# schematic.net
KiCad netlist of a schematic drawn in EasyEDA
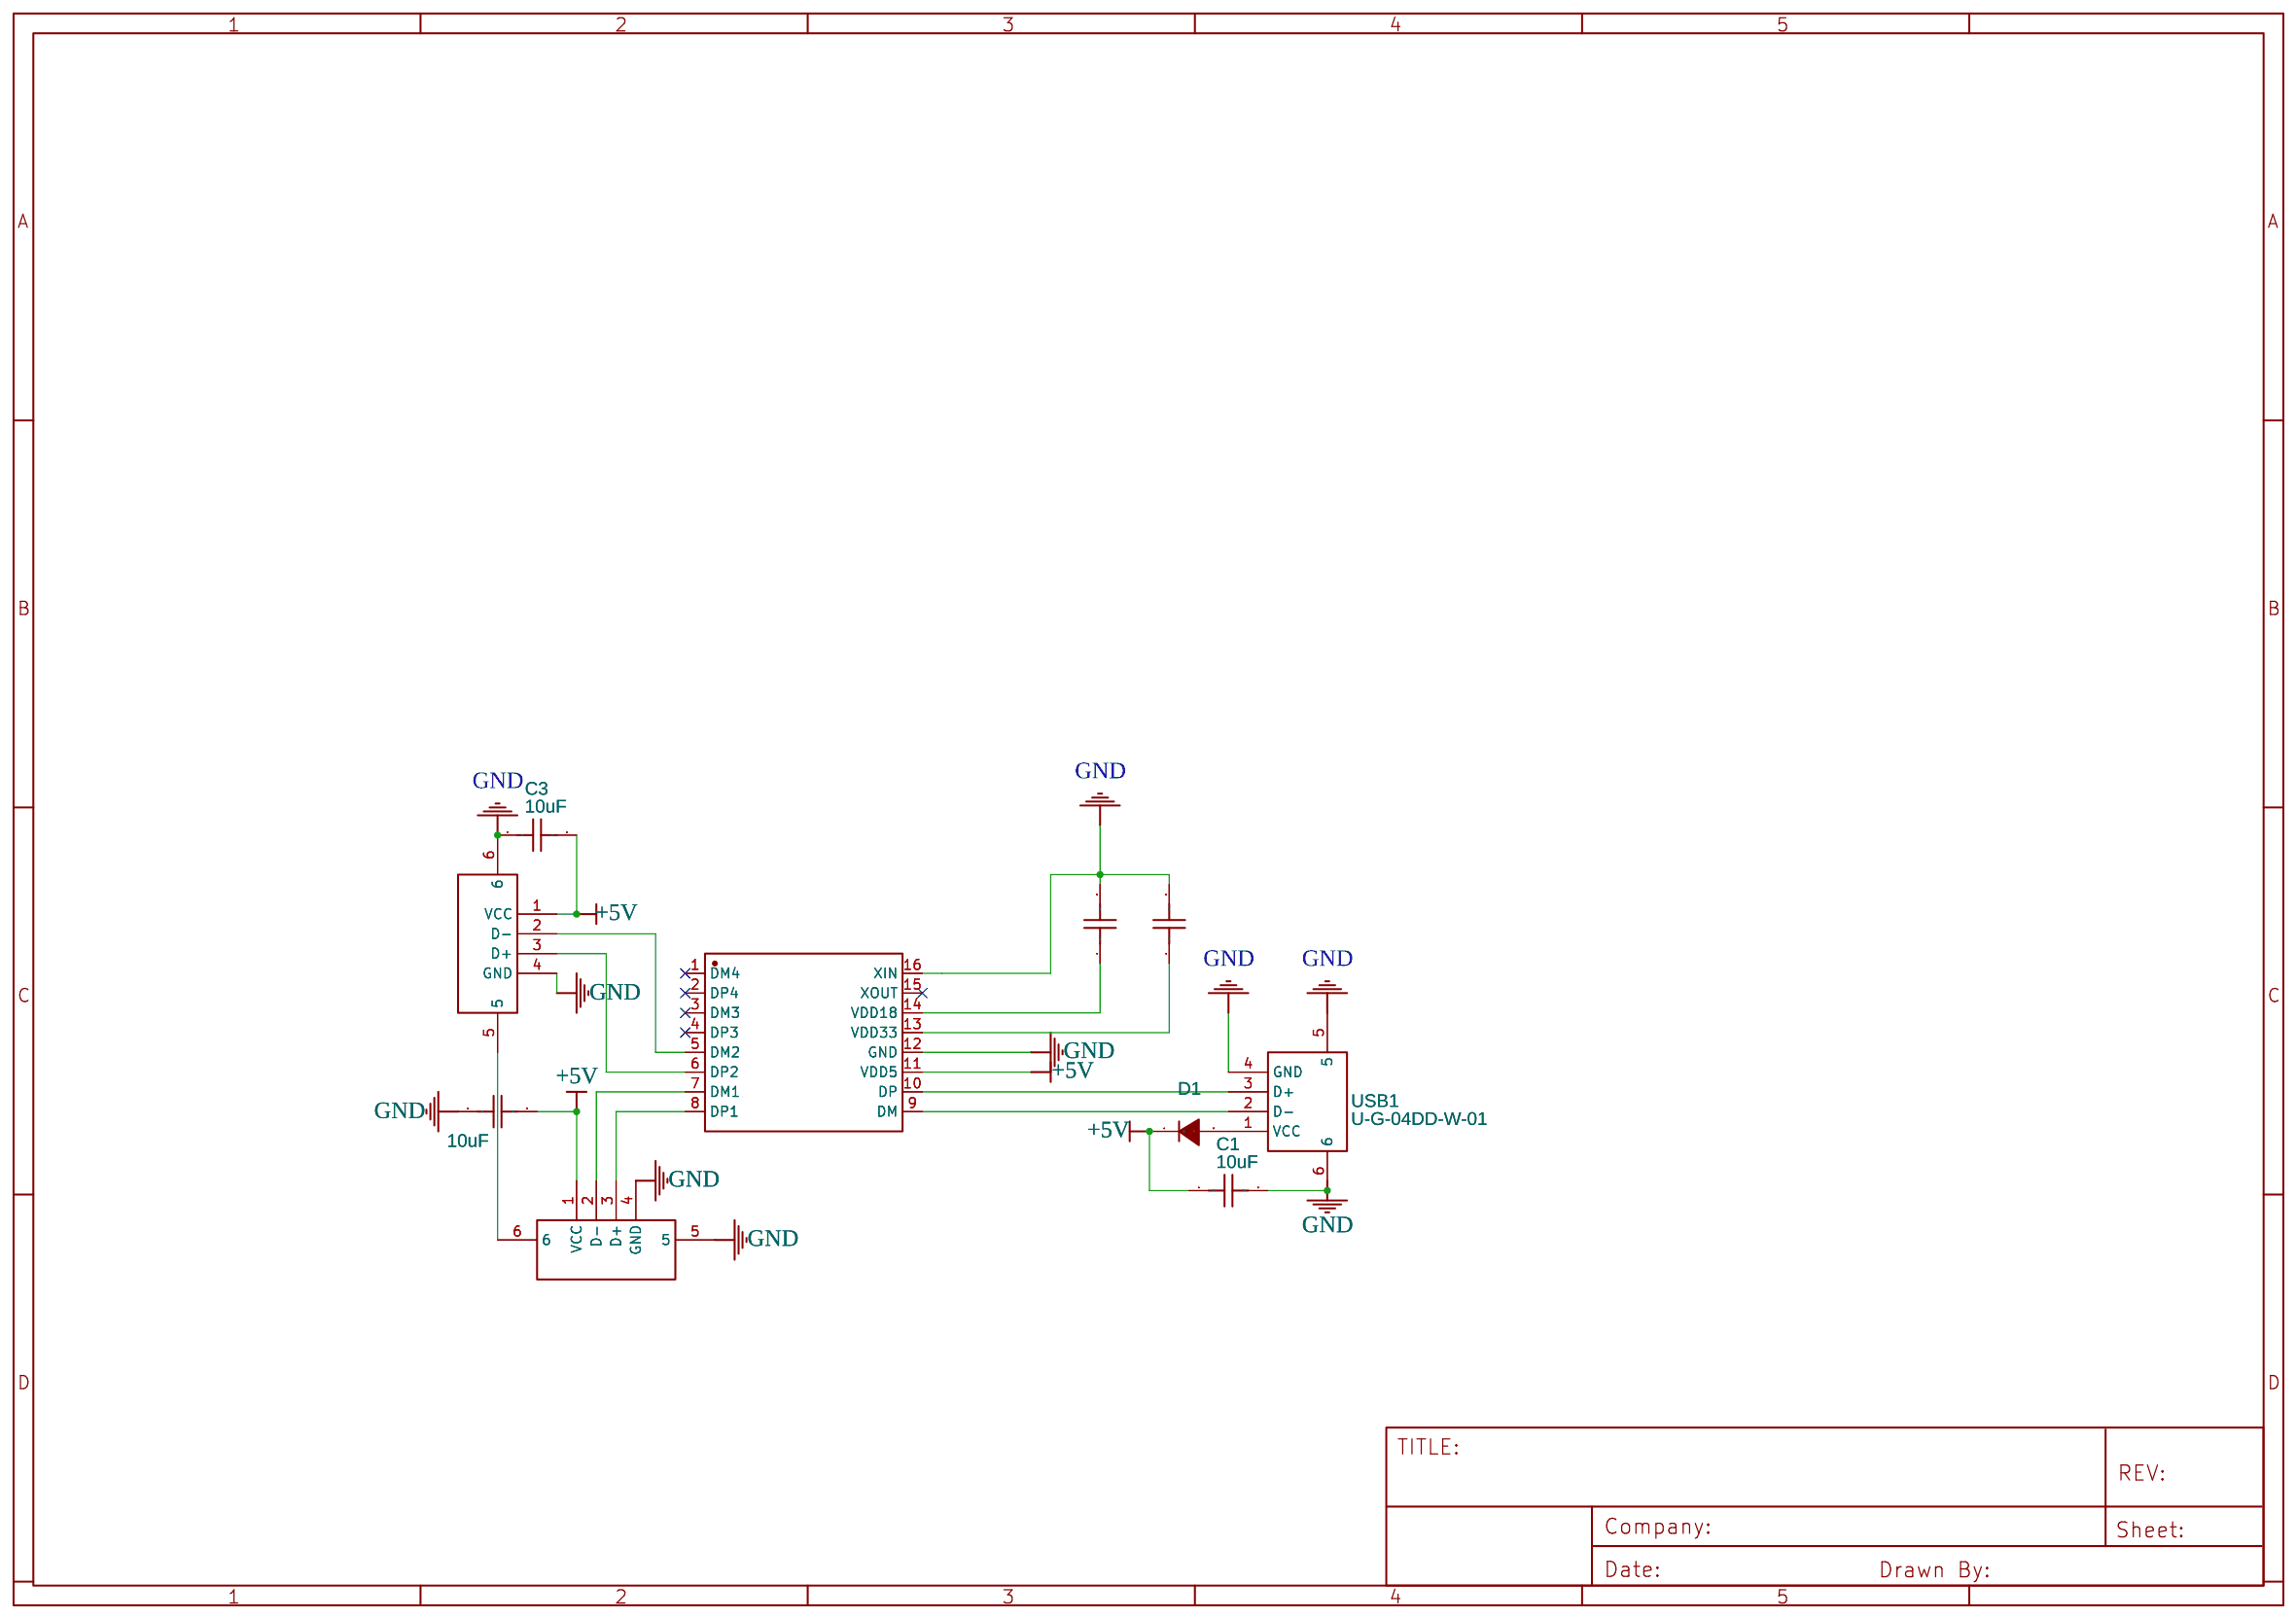
[diagram p0: schematic sheet]

(export (version "E")
  (design (tool "Eeschema 10.0.6"))
  (components
    (comp (ref "C1")
      (value "10uF")
      (fields
        (field (name "Manufacturer Part") "CL10A106KP8NNNC")
        (field (name "Manufacturer") "SAMSUNG(三星)")
      )
      (libsource (lib "") (part "CL10A106KP8NNNC"))
    )
    (comp (ref "C2")
      (value "10uF")
      (fields
        (field (name "Manufacturer Part") "CL10A106KP8NNNC")
        (field (name "Manufacturer") "SAMSUNG(三星)")
      )
      (libsource (lib "") (part "CL10A106KP8NNNC"))
    )
    (comp (ref "C3")
      (value "10uF")
      (fields
        (field (name "Manufacturer Part") "CL10A106KP8NNNC")
        (field (name "Manufacturer") "SAMSUNG(三星)")
      )
      (libsource (lib "") (part "CL10A106KP8NNNC"))
    )
    (comp (ref "C5")
      (value "10uF")
      (fields
        (field (name "Manufacturer Part") "CL10A106KP8NNNC")
        (field (name "Manufacturer") "SAMSUNG(三星)")
      )
      (libsource (lib "") (part "CL10A106KP8NNNC_1"))
    )
    (comp (ref "C6")
      (value "10uF")
      (fields
        (field (name "Manufacturer Part") "CL10A106KP8NNNC")
        (field (name "Manufacturer") "SAMSUNG(三星)")
      )
      (libsource (lib "") (part "CL10A106KP8NNNC_1"))
    )
    (comp (ref "D1")
      (value "NSR0320MW2T1G")
      (fields (field (name "Manufacturer") "onsemi(安森美)"))
      (libsource (lib "") (part "NSR0320MW2T1G"))
    )
    (comp (ref "U1")
      (value "SL2.1A")
      (fields (field (name "Manufacturer") "CoreChips(和芯润德)"))
      (libsource (lib "") (part "SL2.1A"))
    )
    (comp (ref "USB1")
      (value "U-G-04DD-W-01")
      (fields (field (name "Manufacturer Part") "U-G-O4DD-W-1") (field (name "Manufacturer") "韩国韩荣"))
      (libsource (lib "") (part "U-G-04DD-W-01"))
    )
    (comp (ref "USB3")
      (value "USB-AF-90-14.4X13.6-H7.0-DIP")
      (fields (field (name "Manufacturer Part") "903-131A1011D10100") (field (name "Manufacturer") "精拓金"))
      (libsource (lib "") (part "USB-AF-90-14.4X13.6-H7.0-DIP_1"))
    )
    (comp (ref "USB4")
      (value "USB-AF-90-14.4X13.6-H7.0-DIP")
      (fields (field (name "Manufacturer Part") "903-131A1011D10100") (field (name "Manufacturer") "精拓金"))
      (libsource (lib "") (part "USB-AF-90-14.4X13.6-H7.0-DIP"))
    )
  )
  (nets
    (net (code "1") (name "+5V") (class "Default")
      (node (ref "C1") (pin "1") (pinfunction "1_1") (pintype "unspecified"))
      (node (ref "C2") (pin "2") (pinfunction "2_2") (pintype "unspecified"))
      (node (ref "C3") (pin "2") (pinfunction "2_2") (pintype "unspecified"))
      (node (ref "D1") (pin "1") (pinfunction "C_1") (pintype "unspecified"))
      (node (ref "U1") (pin "11") (pinfunction "VDD5_11") (pintype "unspecified"))
      (node (ref "USB3") (pin "1") (pinfunction "VCC_1") (pintype "unspecified"))
      (node (ref "USB4") (pin "1") (pinfunction "VCC_1") (pintype "unspecified"))
    )
    (net (code "2") (name "GND") (class "Default")
      (node (ref "C1") (pin "2") (pinfunction "2_2") (pintype "unspecified"))
      (node (ref "C2") (pin "1") (pinfunction "1_1") (pintype "unspecified"))
      (node (ref "C3") (pin "1") (pinfunction "1_1") (pintype "unspecified"))
      (node (ref "C5") (pin "2") (pinfunction "2_2") (pintype "unspecified"))
      (node (ref "C6") (pin "2") (pinfunction "2_2") (pintype "unspecified"))
      (node (ref "U1") (pin "12") (pinfunction "GND_12") (pintype "unspecified"))
      (node (ref "U1") (pin "16") (pinfunction "XIN_16") (pintype "unspecified"))
      (node (ref "USB1") (pin "4") (pinfunction "GND_4") (pintype "unspecified"))
      (node (ref "USB1") (pin "5") (pinfunction "5_5") (pintype "unspecified"))
      (node (ref "USB1") (pin "6") (pinfunction "6_6") (pintype "unspecified"))
      (node (ref "USB3") (pin "4") (pinfunction "GND_4") (pintype "unspecified"))
      (node (ref "USB3") (pin "5") (pinfunction "5_5") (pintype "unspecified"))
      (node (ref "USB4") (pin "4") (pinfunction "GND_4") (pintype "unspecified"))
      (node (ref "USB4") (pin "6") (pinfunction "6_6") (pintype "unspecified"))
    )
    (net (code "3") (name "Net-(D1-A)") (class "Default")
      (node (ref "D1") (pin "2") (pinfunction "A_2") (pintype "unspecified"))
      (node (ref "USB1") (pin "1") (pinfunction "VCC_1") (pintype "unspecified"))
    )
    (net (code "4") (name "Net-(U1-DM)") (class "Default")
      (node (ref "U1") (pin "9") (pinfunction "DM_9") (pintype "unspecified"))
      (node (ref "USB1") (pin "2") (pinfunction "D-_2") (pintype "unspecified"))
    )
    (net (code "5") (name "Net-(U1-DM1)") (class "Default")
      (node (ref "U1") (pin "7") (pinfunction "DM1_7") (pintype "unspecified"))
      (node (ref "USB3") (pin "2") (pinfunction "D-_2") (pintype "unspecified"))
    )
    (net (code "6") (name "Net-(U1-DM2)") (class "Default")
      (node (ref "U1") (pin "5") (pinfunction "DM2_5") (pintype "unspecified"))
      (node (ref "USB4") (pin "2") (pinfunction "D-_2") (pintype "unspecified"))
    )
    (net (code "7") (name "Net-(U1-DP)") (class "Default")
      (node (ref "U1") (pin "10") (pinfunction "DP_10") (pintype "unspecified"))
      (node (ref "USB1") (pin "3") (pinfunction "D+_3") (pintype "unspecified"))
    )
    (net (code "8") (name "Net-(U1-DP1)") (class "Default")
      (node (ref "U1") (pin "8") (pinfunction "DP1_8") (pintype "unspecified"))
      (node (ref "USB3") (pin "3") (pinfunction "D+_3") (pintype "unspecified"))
    )
    (net (code "9") (name "Net-(U1-DP2)") (class "Default")
      (node (ref "U1") (pin "6") (pinfunction "DP2_6") (pintype "unspecified"))
      (node (ref "USB4") (pin "3") (pinfunction "D+_3") (pintype "unspecified"))
    )
    (net (code "10") (name "Net-(U1-VDD18)") (class "Default")
      (node (ref "C6") (pin "1") (pinfunction "1_1") (pintype "unspecified"))
      (node (ref "U1") (pin "14") (pinfunction "VDD18_14") (pintype "unspecified"))
    )
    (net (code "11") (name "Net-(U1-VDD33)") (class "Default")
      (node (ref "C5") (pin "1") (pinfunction "1_1") (pintype "unspecified"))
      (node (ref "U1") (pin "13") (pinfunction "VDD33_13") (pintype "unspecified"))
    )
    (net (code "12") (name "Net-(USB3-Pad6)") (class "Default")
      (node (ref "USB3") (pin "6") (pinfunction "6_6") (pintype "unspecified"))
      (node (ref "USB4") (pin "5") (pinfunction "5_5") (pintype "unspecified"))
    )
    (net (code "13") (name "unconnected-(U1-DM3-Pad3)") (class "Default")
      (node (ref "U1") (pin "3") (pinfunction "DM3_3") (pintype "unspecified+no_connect"))
    )
    (net (code "14") (name "unconnected-(U1-DM4-Pad1)") (class "Default")
      (node (ref "U1") (pin "1") (pinfunction "DM4_1") (pintype "unspecified+no_connect"))
    )
    (net (code "15") (name "unconnected-(U1-DP3-Pad4)") (class "Default")
      (node (ref "U1") (pin "4") (pinfunction "DP3_4") (pintype "unspecified+no_connect"))
    )
    (net (code "16") (name "unconnected-(U1-DP4-Pad2)") (class "Default")
      (node (ref "U1") (pin "2") (pinfunction "DP4_2") (pintype "unspecified+no_connect"))
    )
    (net (code "17") (name "unconnected-(U1-XOUT-Pad15)") (class "Default")
      (node (ref "U1") (pin "15") (pinfunction "XOUT_15") (pintype "unspecified+no_connect"))
    )
  )
)
